# Keyfinder.net
KiCad netlist of a schematic drawn in Altium Designer
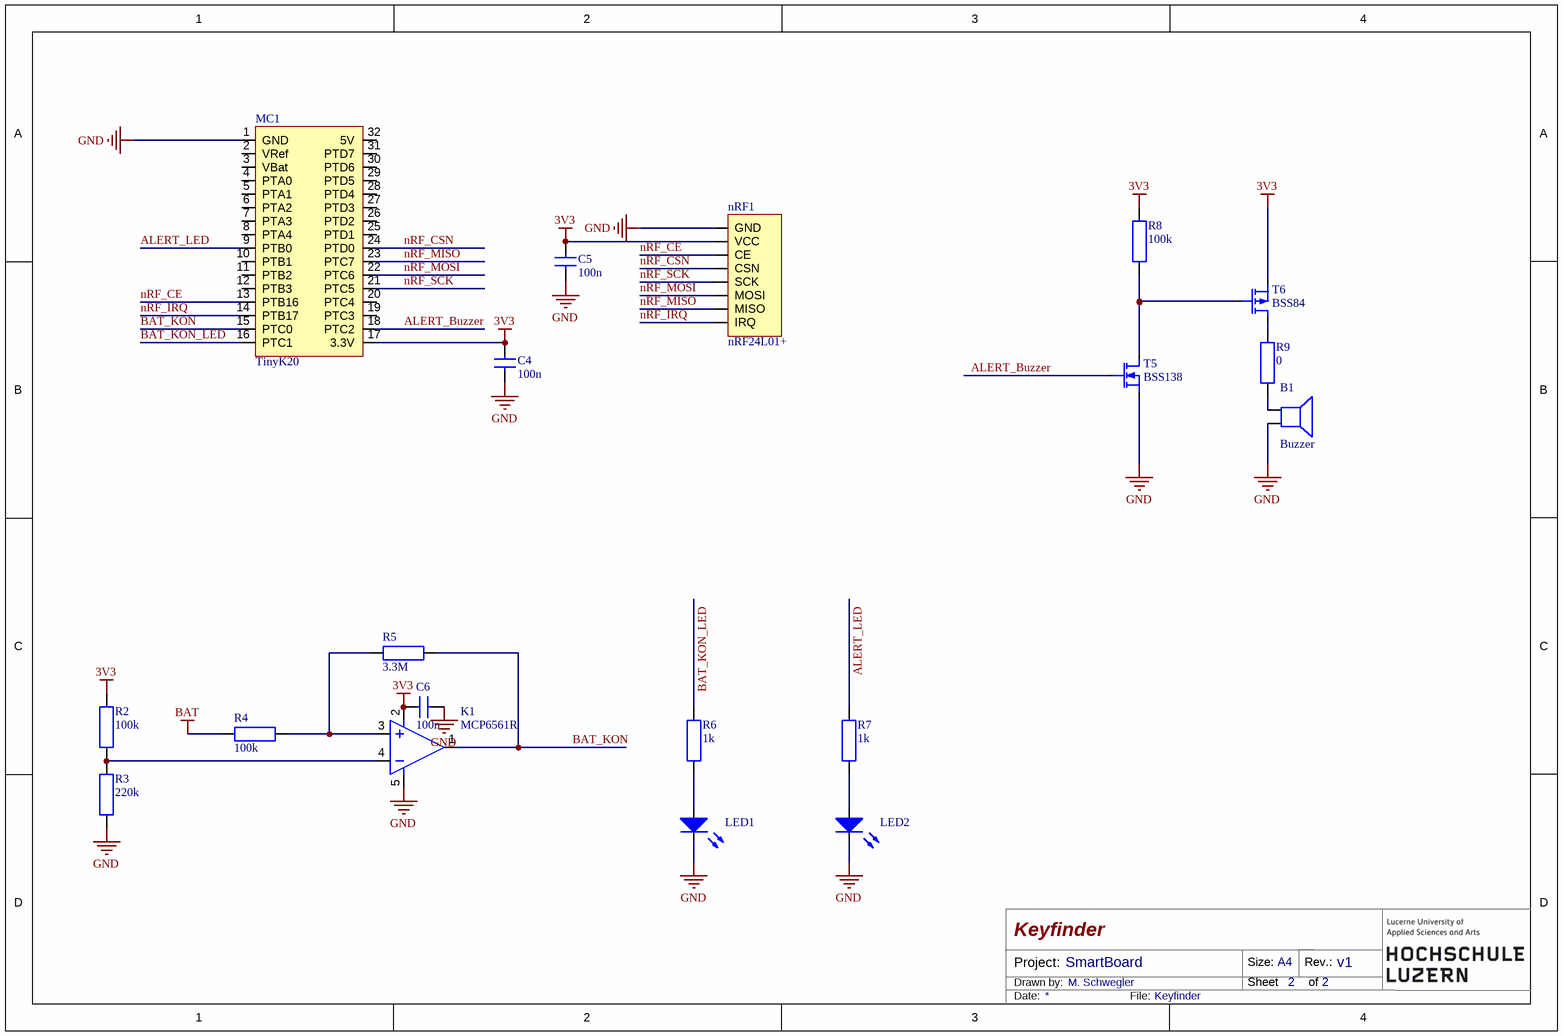
[diagram p0: Keyfinder.SchDoc]

(export (version "E")
  (design (tool "Eeschema 10.0.6"))
  (components
    (comp (ref "B1") (value "Buzzer") (footprint "SIP2") (libsource (lib "DEVICE_HSLU") (part "SPEAKER")))
    (comp (ref "C4")
      (value "100n")
      (footprint "0805_C")
      (description "Normaler Kondensator")
      (libsource (lib "MainBoard") (part "C?"))
    )
    (comp (ref "C5")
      (value "100n")
      (footprint "0805_C")
      (description "Normaler Kondensator")
      (libsource (lib "MainBoard") (part "C?"))
    )
    (comp (ref "C6")
      (value "100n")
      (footprint "0805_C")
      (description "Normaler Kondensator")
      (libsource (lib "MainBoard") (part "C?"))
    )
    (comp (ref "K1") (value "MCP6561R") (footprint "SOT23-5") (libsource (lib "MainBoard") (part "OPAMP")))
    (comp (ref "LED1") (value "~") (footprint "0805_LED") (libsource (lib "Sch_Lib") (part "LED")))
    (comp (ref "LED2") (value "~") (footprint "0805_LED") (libsource (lib "Sch_Lib") (part "LED")))
    (comp (ref "MC1") (value "TinyK20") (footprint "DIP32") (libsource (lib "MainBoard") (part "TinyK20")))
    (comp (ref "nRF1")
      (value "nRF24L01+")
      (footprint "CON_THT_2x4P_RM2.54_Stiftl")
      (libsource (lib "MainBoard") (part "Bluefruit"))
    )
    (comp (ref "R2")
      (value "100k")
      (footprint "0805_R")
      (description "Normaler Widerstand")
      (libsource (lib "MainBoard") (part "R?"))
    )
    (comp (ref "R3")
      (value "220k")
      (footprint "0805_R")
      (description "Normaler Widerstand")
      (libsource (lib "MainBoard") (part "R?"))
    )
    (comp (ref "R4")
      (value "100k")
      (footprint "0805_R")
      (description "Normaler Widerstand")
      (libsource (lib "MainBoard") (part "R?"))
    )
    (comp (ref "R5")
      (value "3.3M")
      (footprint "0805_R")
      (description "Normaler Widerstand")
      (libsource (lib "MainBoard") (part "R?"))
    )
    (comp (ref "R6")
      (value "1k")
      (footprint "0805_R")
      (description "Normaler Widerstand")
      (libsource (lib "MainBoard") (part "R?"))
    )
    (comp (ref "R7")
      (value "1k")
      (footprint "0805_R")
      (description "Normaler Widerstand")
      (libsource (lib "MainBoard") (part "R?"))
    )
    (comp (ref "R8")
      (value "100k")
      (footprint "0805_R")
      (description "Normaler Widerstand")
      (libsource (lib "MainBoard") (part "R?"))
    )
    (comp (ref "R9")
      (value "0")
      (footprint "0805_R")
      (description "Normaler Widerstand")
      (libsource (lib "MainBoard") (part "R?"))
    )
    (comp (ref "T5")
      (value "BSS138")
      (footprint "SOT23-3")
      (description "MOSFET-N 1D,2G,3S")
      (libsource (lib "Sch_Lib") (part "MOSFET-N 1D,2G,3S"))
    )
    (comp (ref "T6")
      (value "BSS84")
      (footprint "SOT23-3")
      (description "MOSFET-P 1D,2G,3S")
      (libsource (lib "Sch_Lib") (part "MOSFET-P 1D,2G,3S"))
    )
  )
  (nets
    (net (code "1") (name "/ALERT_Buzzer") (class "Default")
      (node (ref "MC1") (pin "18") (pinfunction "PTC2_18") (pintype "passive"))
      (node (ref "T5") (pin "1") (pinfunction "G_1") (pintype "passive"))
    )
    (net (code "2") (name "/ALERT_LED") (class "Default")
      (node (ref "MC1") (pin "9") (pinfunction "PTB0_9") (pintype "passive"))
      (node (ref "R7") (pin "1") (pintype "passive"))
    )
    (net (code "3") (name "/BAT_KON") (class "Default")
      (node (ref "K1") (pin "1") (pinfunction "1_1") (pintype "passive"))
      (node (ref "MC1") (pin "15") (pinfunction "PTC0_15") (pintype "passive"))
      (node (ref "R5") (pin "1") (pintype "passive"))
    )
    (net (code "4") (name "/BAT_KON_LED") (class "Default")
      (node (ref "MC1") (pin "16") (pinfunction "PTC1_16") (pintype "passive"))
      (node (ref "R6") (pin "1") (pintype "passive"))
    )
    (net (code "5") (name "/nRF_CE") (class "Default")
      (node (ref "MC1") (pin "13") (pinfunction "PTB16_13") (pintype "passive"))
      (node (ref "nRF1") (pin "3") (pinfunction "CE_3") (pintype "passive"))
    )
    (net (code "6") (name "/nRF_CSN") (class "Default")
      (node (ref "MC1") (pin "24") (pinfunction "PTD0_24") (pintype "passive"))
      (node (ref "nRF1") (pin "4") (pinfunction "CSN_4") (pintype "passive"))
    )
    (net (code "7") (name "/nRF_IRQ") (class "Default")
      (node (ref "MC1") (pin "14") (pinfunction "PTB17_14") (pintype "passive"))
      (node (ref "nRF1") (pin "8") (pinfunction "IRQ_8") (pintype "passive"))
    )
    (net (code "8") (name "/nRF_MISO") (class "Default")
      (node (ref "MC1") (pin "23") (pinfunction "PTC7_23") (pintype "passive"))
      (node (ref "nRF1") (pin "7") (pinfunction "MISO_7") (pintype "passive"))
    )
    (net (code "9") (name "/nRF_MOSI") (class "Default")
      (node (ref "MC1") (pin "22") (pinfunction "PTC6_22") (pintype "passive"))
      (node (ref "nRF1") (pin "6") (pinfunction "MOSI_6") (pintype "passive"))
    )
    (net (code "10") (name "/nRF_SCK") (class "Default")
      (node (ref "MC1") (pin "21") (pinfunction "PTC5_21") (pintype "passive"))
      (node (ref "nRF1") (pin "5") (pinfunction "SCK_5") (pintype "passive"))
    )
    (net (code "11") (name "3V3") (class "Default")
      (node (ref "C4") (pin "2") (pinfunction "2_2") (pintype "passive"))
      (node (ref "C5") (pin "2") (pinfunction "2_2") (pintype "passive"))
      (node (ref "C6") (pin "2") (pinfunction "2_2") (pintype "passive"))
      (node (ref "K1") (pin "2") (pinfunction "2_2") (pintype "passive"))
      (node (ref "MC1") (pin "17") (pinfunction "3.3V_17") (pintype "passive"))
      (node (ref "R2") (pin "1") (pintype "passive"))
      (node (ref "R8") (pin "1") (pintype "passive"))
      (node (ref "T6") (pin "3") (pinfunction "S_3") (pintype "passive"))
      (node (ref "nRF1") (pin "2") (pinfunction "VCC_2") (pintype "passive"))
    )
    (net (code "12") (name "BAT") (class "Default") (node (ref "R4") (pin "2") (pintype "passive")))
    (net (code "13") (name "GND") (class "Default")
      (node (ref "B1") (pin "2") (pintype "passive"))
      (node (ref "C4") (pin "1") (pinfunction "1_1") (pintype "passive"))
      (node (ref "C5") (pin "1") (pinfunction "1_1") (pintype "passive"))
      (node (ref "C6") (pin "1") (pinfunction "1_1") (pintype "passive"))
      (node (ref "K1") (pin "5") (pinfunction "5_5") (pintype "passive"))
      (node (ref "LED1") (pin "2") (pinfunction "K_2") (pintype "passive"))
      (node (ref "LED2") (pin "2") (pinfunction "K_2") (pintype "passive"))
      (node (ref "MC1") (pin "1") (pinfunction "GND_1") (pintype "passive"))
      (node (ref "R3") (pin "2") (pintype "passive"))
      (node (ref "T5") (pin "2") (pinfunction "S_2") (pintype "passive"))
      (node (ref "nRF1") (pin "1") (pinfunction "GND_1") (pintype "passive"))
    )
    (net (code "14") (name "Net-(B1-Pad1)") (class "Default")
      (node (ref "B1") (pin "1") (pintype "passive"))
      (node (ref "R9") (pin "2") (pintype "passive"))
    )
    (net (code "15") (name "Net-(K1-Pad3)") (class "Default")
      (node (ref "K1") (pin "3") (pinfunction "3_3") (pintype "passive"))
      (node (ref "R4") (pin "1") (pintype "passive"))
      (node (ref "R5") (pin "2") (pintype "passive"))
    )
    (net (code "16") (name "Net-(K1-Pad4)") (class "Default")
      (node (ref "K1") (pin "4") (pinfunction "4_4") (pintype "passive"))
      (node (ref "R2") (pin "2") (pintype "passive"))
      (node (ref "R3") (pin "1") (pintype "passive"))
    )
    (net (code "17") (name "Net-(LED1-A)") (class "Default")
      (node (ref "LED1") (pin "1") (pinfunction "A_1") (pintype "passive"))
      (node (ref "R6") (pin "2") (pintype "passive"))
    )
    (net (code "18") (name "Net-(LED2-A)") (class "Default")
      (node (ref "LED2") (pin "1") (pinfunction "A_1") (pintype "passive"))
      (node (ref "R7") (pin "2") (pintype "passive"))
    )
    (net (code "19") (name "Net-(T5-D)") (class "Default")
      (node (ref "R8") (pin "2") (pintype "passive"))
      (node (ref "T5") (pin "3") (pinfunction "D_3") (pintype "passive"))
      (node (ref "T6") (pin "2") (pinfunction "G_2") (pintype "passive"))
    )
    (net (code "20") (name "Net-(T6-D)") (class "Default")
      (node (ref "R9") (pin "1") (pintype "passive"))
      (node (ref "T6") (pin "1") (pinfunction "D_1") (pintype "passive"))
    )
    (net (code "21") (name "unconnected-(MC1-5V-Pad32)") (class "Default")
      (node (ref "MC1") (pin "32") (pinfunction "5V_32") (pintype "passive"))
    )
    (net (code "22") (name "unconnected-(MC1-PTA0-Pad4)") (class "Default")
      (node (ref "MC1") (pin "4") (pinfunction "PTA0_4") (pintype "passive"))
    )
    (net (code "23") (name "unconnected-(MC1-PTA1-Pad5)") (class "Default")
      (node (ref "MC1") (pin "5") (pinfunction "PTA1_5") (pintype "passive"))
    )
    (net (code "24") (name "unconnected-(MC1-PTA2-Pad6)") (class "Default")
      (node (ref "MC1") (pin "6") (pinfunction "PTA2_6") (pintype "passive"))
    )
    (net (code "25") (name "unconnected-(MC1-PTA3-Pad7)") (class "Default")
      (node (ref "MC1") (pin "7") (pinfunction "PTA3_7") (pintype "passive"))
    )
    (net (code "26") (name "unconnected-(MC1-PTA4-Pad8)") (class "Default")
      (node (ref "MC1") (pin "8") (pinfunction "PTA4_8") (pintype "passive"))
    )
    (net (code "27") (name "unconnected-(MC1-PTB1-Pad10)") (class "Default")
      (node (ref "MC1") (pin "10") (pinfunction "PTB1_10") (pintype "passive"))
    )
    (net (code "28") (name "unconnected-(MC1-PTB2-Pad11)") (class "Default")
      (node (ref "MC1") (pin "11") (pinfunction "PTB2_11") (pintype "passive"))
    )
    (net (code "29") (name "unconnected-(MC1-PTB3-Pad12)") (class "Default")
      (node (ref "MC1") (pin "12") (pinfunction "PTB3_12") (pintype "passive"))
    )
    (net (code "30") (name "unconnected-(MC1-PTC3-Pad19)") (class "Default")
      (node (ref "MC1") (pin "19") (pinfunction "PTC3_19") (pintype "passive"))
    )
    (net (code "31") (name "unconnected-(MC1-PTC4-Pad20)") (class "Default")
      (node (ref "MC1") (pin "20") (pinfunction "PTC4_20") (pintype "passive"))
    )
    (net (code "32") (name "unconnected-(MC1-PTD1-Pad25)") (class "Default")
      (node (ref "MC1") (pin "25") (pinfunction "PTD1_25") (pintype "passive"))
    )
    (net (code "33") (name "unconnected-(MC1-PTD2-Pad26)") (class "Default")
      (node (ref "MC1") (pin "26") (pinfunction "PTD2_26") (pintype "passive"))
    )
    (net (code "34") (name "unconnected-(MC1-PTD3-Pad27)") (class "Default")
      (node (ref "MC1") (pin "27") (pinfunction "PTD3_27") (pintype "passive"))
    )
    (net (code "35") (name "unconnected-(MC1-PTD4-Pad28)") (class "Default")
      (node (ref "MC1") (pin "28") (pinfunction "PTD4_28") (pintype "passive"))
    )
    (net (code "36") (name "unconnected-(MC1-PTD5-Pad29)") (class "Default")
      (node (ref "MC1") (pin "29") (pinfunction "PTD5_29") (pintype "passive"))
    )
    (net (code "37") (name "unconnected-(MC1-PTD6-Pad30)") (class "Default")
      (node (ref "MC1") (pin "30") (pinfunction "PTD6_30") (pintype "passive"))
    )
    (net (code "38") (name "unconnected-(MC1-PTD7-Pad31)") (class "Default")
      (node (ref "MC1") (pin "31") (pinfunction "PTD7_31") (pintype "passive"))
    )
    (net (code "39") (name "unconnected-(MC1-VBat-Pad3)") (class "Default")
      (node (ref "MC1") (pin "3") (pinfunction "VBat_3") (pintype "passive"))
    )
    (net (code "40") (name "unconnected-(MC1-VRef-Pad2)") (class "Default")
      (node (ref "MC1") (pin "2") (pinfunction "VRef_2") (pintype "passive"))
    )
  )
)
